# Strange_V3_2021-09-19_20-10-57.net
KiCad netlist of a schematic drawn in EasyEDA
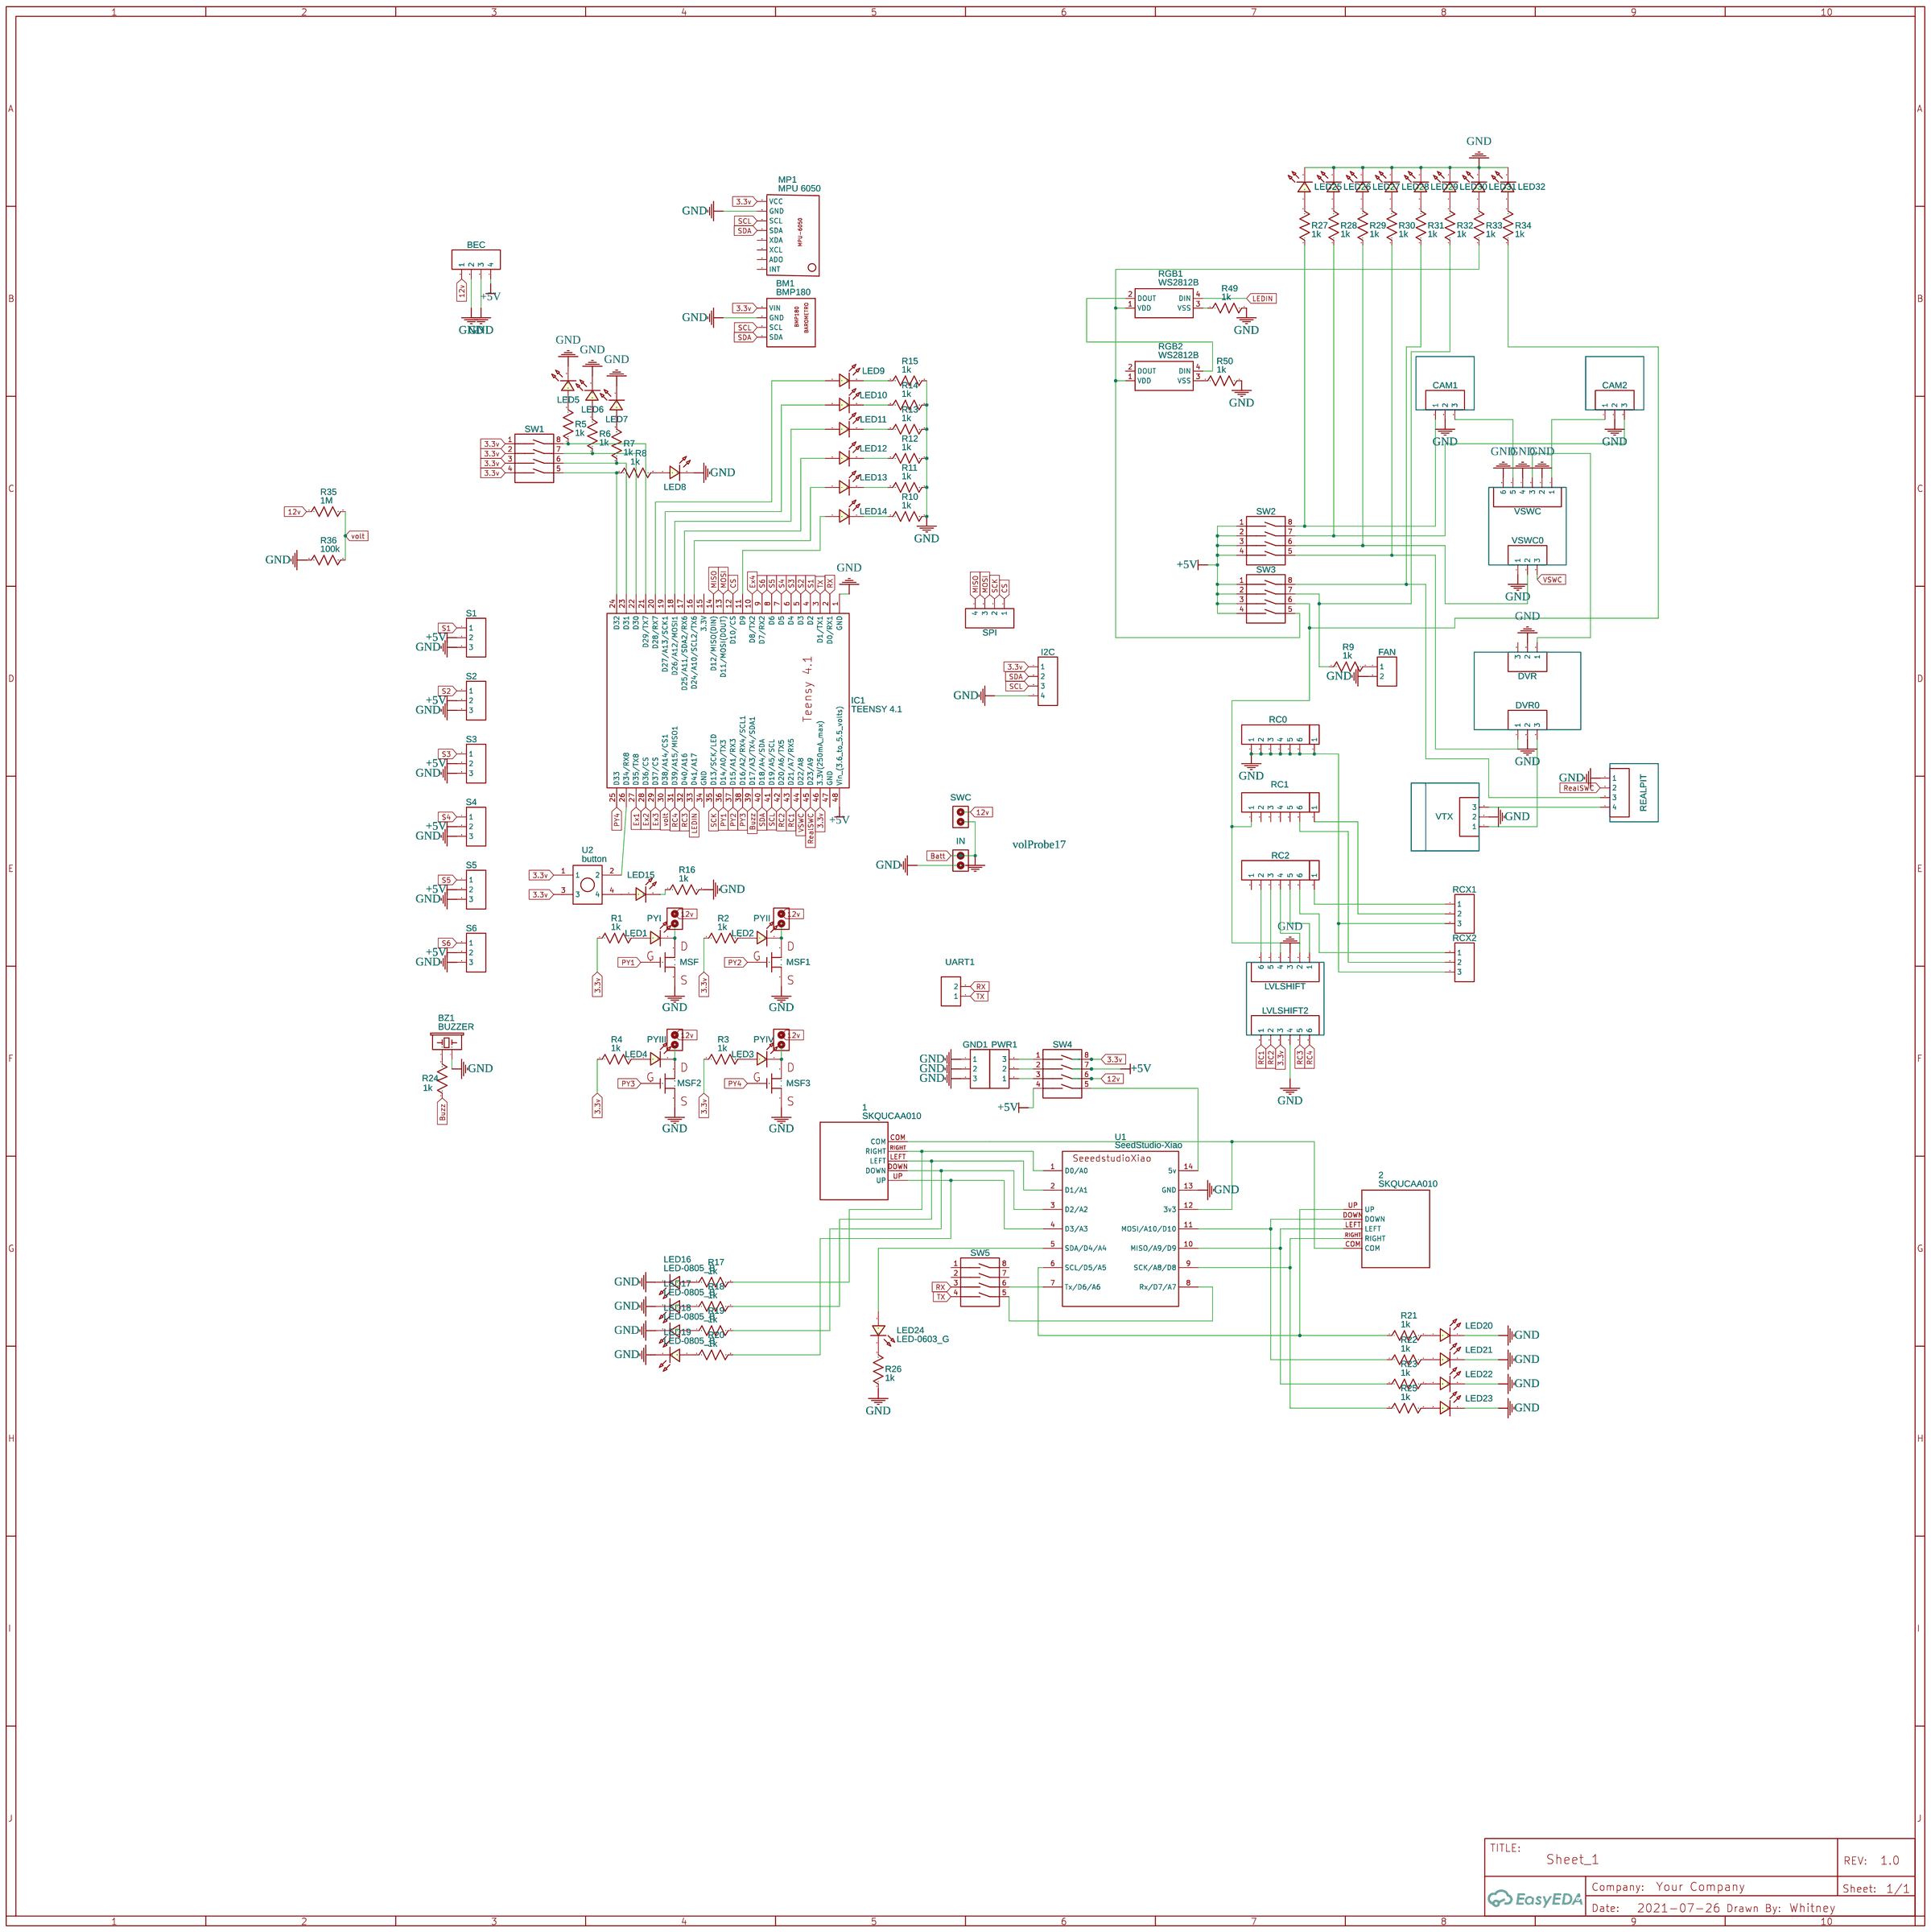
[diagram p0: schematic sheet]

(export (version "E")
  (design (tool "Eeschema 10.0.6"))
  (components
    (comp (ref "1") (value "SKQUCAA010") (libsource (lib "") (part "SKQUCAA010_1")))
    (comp (ref "2") (value "SKQUCAA010") (libsource (lib "") (part "SKQUCAA010")))
    (comp (ref "BEC")
      (value "HDR-M-2.54_1x4")
      (fields (field (name "BOM_Supplier Part") "C124378"))
      (libsource (lib "") (part "HDR-M-2.54_1x4"))
    )
    (comp (ref "BM1") (value "BMP180") (libsource (lib "") (part "BMP180")))
    (comp (ref "BZ1") (value "BUZZER") (libsource (lib "") (part "BUZZER")))
    (comp (ref "CAM1")
      (value "HDR-M-2.54_1x3")
      (fields (field (name "BOM_Supplier Part") "C180248"))
      (libsource (lib "") (part "HDR-M-2.54_1x3_6"))
    )
    (comp (ref "CAM2")
      (value "HDR-M-2.54_1x3")
      (fields (field (name "BOM_Supplier Part") "C180248"))
      (libsource (lib "") (part "HDR-M-2.54_1x3_6"))
    )
    (comp (ref "DVR")
      (value "HDR-M-2.54_1x3")
      (fields (field (name "BOM_Supplier Part") "C180248"))
      (libsource (lib "") (part "HDR-M-2.54_1x3_8"))
    )
    (comp (ref "DVR0")
      (value "HDR-M-2.54_1x3")
      (fields (field (name "BOM_Supplier Part") "C180248"))
      (libsource (lib "") (part "HDR-M-2.54_1x3_3"))
    )
    (comp (ref "FAN")
      (value "HDR-M-2.54_1x2")
      (fields (field (name "BOM_Supplier Part") "C124375"))
      (libsource (lib "") (part "HDR-M-2.54_1x2"))
    )
    (comp (ref "GND1")
      (value "HDR-M-2.54_1x3")
      (fields (field (name "BOM_Supplier Part") "C180248"))
      (libsource (lib "") (part "HDR-M-2.54_1x3"))
    )
    (comp (ref "I2C")
      (value "HDR-M-2.54_1x4")
      (fields (field (name "BOM_Supplier Part") "C124378"))
      (libsource (lib "") (part "HDR-M-2.54_1x4_3"))
    )
    (comp (ref "IC1")
      (value "TEENSY 4.1")
      (fields
        (field (name "BOM_Manufacturer Part") "Teensy 4.1")
        (field (name "BOM_Supplier Part") "474-DEV-16771")
      )
      (libsource (lib "") (part "TEENSY 4.1"))
    )
    (comp (ref "IN") (value "Screw terminal 2x1") (libsource (lib "") (part "Screw terminal 2x1_3")))
    (comp (ref "J6")
      (value "HDR-M-2.54_1x1")
      (fields (field (name "BOM_Supplier Part") "C81276"))
      (libsource (lib "") (part "HDR-M-2.54_1x1"))
    )
    (comp (ref "J10")
      (value "HDR-M-2.54_1x1")
      (fields (field (name "BOM_Supplier Part") "C81276"))
      (libsource (lib "") (part "HDR-M-2.54_1x1"))
    )
    (comp (ref "J11")
      (value "HDR-M-2.54_1x1")
      (fields (field (name "BOM_Supplier Part") "C81276"))
      (libsource (lib "") (part "HDR-M-2.54_1x1"))
    )
    (comp (ref "LED1")
      (value "LED-0805_G")
      (fields (field (name "BOM_Manufacturer Part") "NCD0805G1") (field (name "BOM_Supplier Part") "C84260"))
      (libsource (lib "") (part "LED-0805_G_1"))
    )
    (comp (ref "LED2")
      (value "LED-0805_G")
      (fields (field (name "BOM_Manufacturer Part") "NCD0805G1") (field (name "BOM_Supplier Part") "C84260"))
      (libsource (lib "") (part "LED-0805_G_1"))
    )
    (comp (ref "LED3")
      (value "LED-0805_G")
      (fields (field (name "BOM_Manufacturer Part") "NCD0805G1") (field (name "BOM_Supplier Part") "C84260"))
      (libsource (lib "") (part "LED-0805_G_1"))
    )
    (comp (ref "LED4")
      (value "LED-0805_G")
      (fields (field (name "BOM_Manufacturer Part") "NCD0805G1") (field (name "BOM_Supplier Part") "C84260"))
      (libsource (lib "") (part "LED-0805_G_1"))
    )
    (comp (ref "LED5")
      (value "LED-0805_G")
      (fields (field (name "BOM_Manufacturer Part") "NCD0805G1") (field (name "BOM_Supplier Part") "C84260"))
      (libsource (lib "") (part "LED-0805_G"))
    )
    (comp (ref "LED6")
      (value "LED-0805_G")
      (fields (field (name "BOM_Manufacturer Part") "NCD0805G1") (field (name "BOM_Supplier Part") "C84260"))
      (libsource (lib "") (part "LED-0805_G"))
    )
    (comp (ref "LED7")
      (value "LED-0805_G")
      (fields (field (name "BOM_Manufacturer Part") "NCD0805G1") (field (name "BOM_Supplier Part") "C84260"))
      (libsource (lib "") (part "LED-0805_G"))
    )
    (comp (ref "LED8")
      (value "LED-0805_G")
      (fields (field (name "BOM_Manufacturer Part") "NCD0805G1") (field (name "BOM_Supplier Part") "C84260"))
      (libsource (lib "") (part "LED-0805_G_1"))
    )
    (comp (ref "LED9")
      (value "LED-0603_R")
      (fields
        (field (name "BOM_Manufacturer Part") "19-217/R6C-AL1M2VY/3T")
        (field (name "BOM_Supplier Part") "C72044")
      )
      (libsource (lib "") (part "LED-0603_R"))
    )
    (comp (ref "LED10")
      (value "LED-0603_R")
      (fields
        (field (name "BOM_Manufacturer Part") "19-217/R6C-AL1M2VY/3T")
        (field (name "BOM_Supplier Part") "C72044")
      )
      (libsource (lib "") (part "LED-0603_R"))
    )
    (comp (ref "LED11")
      (value "LED-0603_R")
      (fields
        (field (name "BOM_Manufacturer Part") "19-217/R6C-AL1M2VY/3T")
        (field (name "BOM_Supplier Part") "C72044")
      )
      (libsource (lib "") (part "LED-0603_R"))
    )
    (comp (ref "LED12")
      (value "LED-0603_R")
      (fields
        (field (name "BOM_Manufacturer Part") "19-217/R6C-AL1M2VY/3T")
        (field (name "BOM_Supplier Part") "C72044")
      )
      (libsource (lib "") (part "LED-0603_R"))
    )
    (comp (ref "LED13")
      (value "LED-0603_R")
      (fields
        (field (name "BOM_Manufacturer Part") "19-217/R6C-AL1M2VY/3T")
        (field (name "BOM_Supplier Part") "C72044")
      )
      (libsource (lib "") (part "LED-0603_R"))
    )
    (comp (ref "LED14")
      (value "LED-0603_R")
      (fields
        (field (name "BOM_Manufacturer Part") "19-217/R6C-AL1M2VY/3T")
        (field (name "BOM_Supplier Part") "C72044")
      )
      (libsource (lib "") (part "LED-0603_R"))
    )
    (comp (ref "LED15")
      (value "LED-0603_R")
      (fields
        (field (name "BOM_Manufacturer Part") "19-217/R6C-AL1M2VY/3T")
        (field (name "BOM_Supplier Part") "C72044")
      )
      (libsource (lib "") (part "LED-0603_R"))
    )
    (comp (ref "LED16")
      (value "LED-0805_B")
      (fields
        (field (name "BOM_Manufacturer Part") "D-B080508B1-KS2")
        (field (name "BOM_Supplier Part") "C108412")
      )
      (libsource (lib "") (part "LED-0805_B"))
    )
    (comp (ref "LED17")
      (value "LED-0805_B")
      (fields
        (field (name "BOM_Manufacturer Part") "D-B080508B1-KS2")
        (field (name "BOM_Supplier Part") "C108412")
      )
      (libsource (lib "") (part "LED-0805_B"))
    )
    (comp (ref "LED18")
      (value "LED-0805_B")
      (fields
        (field (name "BOM_Manufacturer Part") "D-B080508B1-KS2")
        (field (name "BOM_Supplier Part") "C108412")
      )
      (libsource (lib "") (part "LED-0805_B"))
    )
    (comp (ref "LED19")
      (value "LED-0805_B")
      (fields
        (field (name "BOM_Manufacturer Part") "D-B080508B1-KS2")
        (field (name "BOM_Supplier Part") "C108412")
      )
      (libsource (lib "") (part "LED-0805_B"))
    )
    (comp (ref "LED20")
      (value "LED-0805_B")
      (fields
        (field (name "BOM_Manufacturer Part") "D-B080508B1-KS2")
        (field (name "BOM_Supplier Part") "C108412")
      )
      (libsource (lib "") (part "LED-0805_B_1"))
    )
    (comp (ref "LED21")
      (value "LED-0805_B")
      (fields
        (field (name "BOM_Manufacturer Part") "D-B080508B1-KS2")
        (field (name "BOM_Supplier Part") "C108412")
      )
      (libsource (lib "") (part "LED-0805_B_1"))
    )
    (comp (ref "LED22")
      (value "LED-0805_B")
      (fields
        (field (name "BOM_Manufacturer Part") "D-B080508B1-KS2")
        (field (name "BOM_Supplier Part") "C108412")
      )
      (libsource (lib "") (part "LED-0805_B_1"))
    )
    (comp (ref "LED23")
      (value "LED-0805_B")
      (fields
        (field (name "BOM_Manufacturer Part") "D-B080508B1-KS2")
        (field (name "BOM_Supplier Part") "C108412")
      )
      (libsource (lib "") (part "LED-0805_B_1"))
    )
    (comp (ref "LED24")
      (value "LED-0603_G")
      (fields
        (field (name "BOM_Manufacturer Part") "19-217/GHC-YR1S2/3T")
        (field (name "BOM_Supplier Part") "C72043")
      )
      (libsource (lib "") (part "LED-0603_G"))
    )
    (comp (ref "LED25")
      (value "LED-TH-3mm_R")
      (fields
        (field (name "BOM_Manufacturer Part") "204-10SDRD/S530-A3-L")
        (field (name "BOM_Supplier Part") "C84774")
      )
      (libsource (lib "") (part "LED-TH-3mm_R"))
    )
    (comp (ref "LED26")
      (value "LED-TH-3mm_R")
      (fields
        (field (name "BOM_Manufacturer Part") "204-10SDRD/S530-A3-L")
        (field (name "BOM_Supplier Part") "C84774")
      )
      (libsource (lib "") (part "LED-TH-3mm_R"))
    )
    (comp (ref "LED27")
      (value "LED-TH-3mm_R")
      (fields
        (field (name "BOM_Manufacturer Part") "204-10SDRD/S530-A3-L")
        (field (name "BOM_Supplier Part") "C84774")
      )
      (libsource (lib "") (part "LED-TH-3mm_R"))
    )
    (comp (ref "LED28")
      (value "LED-TH-3mm_R")
      (fields
        (field (name "BOM_Manufacturer Part") "204-10SDRD/S530-A3-L")
        (field (name "BOM_Supplier Part") "C84774")
      )
      (libsource (lib "") (part "LED-TH-3mm_R"))
    )
    (comp (ref "LED29")
      (value "LED-TH-3mm_R")
      (fields
        (field (name "BOM_Manufacturer Part") "204-10SDRD/S530-A3-L")
        (field (name "BOM_Supplier Part") "C84774")
      )
      (libsource (lib "") (part "LED-TH-3mm_R"))
    )
    (comp (ref "LED30")
      (value "LED-TH-3mm_R")
      (fields
        (field (name "BOM_Manufacturer Part") "204-10SDRD/S530-A3-L")
        (field (name "BOM_Supplier Part") "C84774")
      )
      (libsource (lib "") (part "LED-TH-3mm_R"))
    )
    (comp (ref "LED31")
      (value "LED-TH-3mm_R")
      (fields
        (field (name "BOM_Manufacturer Part") "204-10SDRD/S530-A3-L")
        (field (name "BOM_Supplier Part") "C84774")
      )
      (libsource (lib "") (part "LED-TH-3mm_R"))
    )
    (comp (ref "LED32")
      (value "LED-TH-3mm_R")
      (fields
        (field (name "BOM_Manufacturer Part") "204-10SDRD/S530-A3-L")
        (field (name "BOM_Supplier Part") "C84774")
      )
      (libsource (lib "") (part "LED-TH-3mm_R"))
    )
    (comp (ref "LVLSHIFT")
      (value "HDR-M-2.54_1x6")
      (fields (field (name "BOM_Supplier Part") "C190819"))
      (libsource (lib "") (part "HDR-M-2.54_1x6_3"))
    )
    (comp (ref "LVLSHIFT2")
      (value "HDR-M-2.54_1x6")
      (fields (field (name "BOM_Supplier Part") "C190819"))
      (libsource (lib "") (part "HDR-M-2.54_1x6_1"))
    )
    (comp (ref "MP1") (value "MPU 6050") (libsource (lib "") (part "MPU 6050")))
    (comp (ref "MSF") (value "RFP30N06LE") (libsource (lib "") (part "RFP30N06LE")))
    (comp (ref "MSF1") (value "RFP30N06LE") (libsource (lib "") (part "RFP30N06LE")))
    (comp (ref "MSF2") (value "RFP30N06LE") (libsource (lib "") (part "RFP30N06LE")))
    (comp (ref "MSF3") (value "RFP30N06LE") (libsource (lib "") (part "RFP30N06LE")))
    (comp (ref "PWR1")
      (value "HDR-M-2.54_1x3")
      (fields (field (name "BOM_Supplier Part") "C180248"))
      (libsource (lib "") (part "HDR-M-2.54_1x3_7"))
    )
    (comp (ref "PYI") (value "Screw terminal 2x1") (libsource (lib "") (part "Screw terminal 2x1")))
    (comp (ref "PYII") (value "Screw terminal 2x1") (libsource (lib "") (part "Screw terminal 2x1_2")))
    (comp (ref "PYIII") (value "Screw terminal 2x1") (libsource (lib "") (part "Screw terminal 2x1_4")))
    (comp (ref "PYIV") (value "Screw terminal 2x1") (libsource (lib "") (part "Screw terminal 2x1_1")))
    (comp (ref "R1") (value "1k") (libsource (lib "") (part "R_AXIAL-0.3_US_1")))
    (comp (ref "R2") (value "1k") (libsource (lib "") (part "R_AXIAL-0.3_US_1")))
    (comp (ref "R3") (value "1k") (libsource (lib "") (part "R_AXIAL-0.3_US_1")))
    (comp (ref "R4") (value "1k") (libsource (lib "") (part "R_AXIAL-0.3_US_1")))
    (comp (ref "R5") (value "1k") (libsource (lib "") (part "R_AXIAL-0.3_US")))
    (comp (ref "R6") (value "1k") (libsource (lib "") (part "R_AXIAL-0.3_US")))
    (comp (ref "R7") (value "1k") (libsource (lib "") (part "R_AXIAL-0.3_US")))
    (comp (ref "R8") (value "1k") (libsource (lib "") (part "R_AXIAL-0.3_US_1")))
    (comp (ref "R9") (value "1k") (libsource (lib "") (part "R_AXIAL-0.3_US_1")))
    (comp (ref "R10") (value "1k") (libsource (lib "") (part "R_AXIAL-0.3_US_1")))
    (comp (ref "R11") (value "1k") (libsource (lib "") (part "R_AXIAL-0.3_US_1")))
    (comp (ref "R12") (value "1k") (libsource (lib "") (part "R_AXIAL-0.3_US_1")))
    (comp (ref "R13") (value "1k") (libsource (lib "") (part "R_AXIAL-0.3_US_1")))
    (comp (ref "R14") (value "1k") (libsource (lib "") (part "R_AXIAL-0.3_US_1")))
    (comp (ref "R15") (value "1k") (libsource (lib "") (part "R_AXIAL-0.3_US_1")))
    (comp (ref "R16") (value "1k") (libsource (lib "") (part "R_AXIAL-0.3_US_1")))
    (comp (ref "R17") (value "1k") (libsource (lib "") (part "R_0603_US")))
    (comp (ref "R18") (value "1k") (libsource (lib "") (part "R_0603_US")))
    (comp (ref "R19") (value "1k") (libsource (lib "") (part "R_0603_US")))
    (comp (ref "R20") (value "1k") (libsource (lib "") (part "R_0603_US")))
    (comp (ref "R21") (value "1k") (libsource (lib "") (part "R_0603_US")))
    (comp (ref "R22") (value "1k") (libsource (lib "") (part "R_0603_US")))
    (comp (ref "R23") (value "1k") (libsource (lib "") (part "R_0603_US")))
    (comp (ref "R24") (value "1k") (libsource (lib "") (part "R_AXIAL-0.3_US")))
    (comp (ref "R25") (value "1k") (libsource (lib "") (part "R_0603_US")))
    (comp (ref "R26") (value "1k") (libsource (lib "") (part "R_0603_US_1")))
    (comp (ref "R27") (value "1k") (libsource (lib "") (part "R_AXIAL-0.3_US")))
    (comp (ref "R28") (value "1k") (libsource (lib "") (part "R_AXIAL-0.3_US")))
    (comp (ref "R29") (value "1k") (libsource (lib "") (part "R_AXIAL-0.3_US")))
    (comp (ref "R30") (value "1k") (libsource (lib "") (part "R_AXIAL-0.3_US")))
    (comp (ref "R31") (value "1k") (libsource (lib "") (part "R_AXIAL-0.3_US")))
    (comp (ref "R32") (value "1k") (libsource (lib "") (part "R_AXIAL-0.3_US")))
    (comp (ref "R33") (value "1k") (libsource (lib "") (part "R_AXIAL-0.3_US")))
    (comp (ref "R34") (value "1k") (libsource (lib "") (part "R_AXIAL-0.3_US")))
    (comp (ref "R35") (value "1M") (libsource (lib "") (part "R_AXIAL-0.3_US_1")))
    (comp (ref "R36") (value "100k") (libsource (lib "") (part "R_AXIAL-0.3_US_1")))
    (comp (ref "R49") (value "1k") (libsource (lib "") (part "R_0603_US")))
    (comp (ref "R50") (value "1k") (libsource (lib "") (part "R_0603_US")))
    (comp (ref "RC0")
      (value "HDR-M-2.54_1x6")
      (fields (field (name "BOM_Supplier Part") "C190819"))
      (libsource (lib "") (part "HDR-M-2.54_1x6_2"))
    )
    (comp (ref "RC1")
      (value "HDR-M-2.54_1x6")
      (fields (field (name "BOM_Supplier Part") "C190819"))
      (libsource (lib "") (part "HDR-M-2.54_1x6_2"))
    )
    (comp (ref "RC2")
      (value "HDR-M-2.54_1x6")
      (fields (field (name "BOM_Supplier Part") "C190819"))
      (libsource (lib "") (part "HDR-M-2.54_1x6_2"))
    )
    (comp (ref "RCX1")
      (value "HDR-M-2.54_1x3")
      (fields (field (name "BOM_Supplier Part") "C180248"))
      (libsource (lib "") (part "HDR-M-2.54_1x3_1"))
    )
    (comp (ref "RCX2")
      (value "HDR-M-2.54_1x3")
      (fields (field (name "BOM_Supplier Part") "C180248"))
      (libsource (lib "") (part "HDR-M-2.54_1x3_1"))
    )
    (comp (ref "REALPIT")
      (value "HDR-M-2.54_1x4")
      (fields (field (name "BOM_Supplier Part") "C124378"))
      (libsource (lib "") (part "HDR-M-2.54_1x4_1"))
    )
    (comp (ref "RGB1") (value "WS2812B") (libsource (lib "") (part "WS2812B")))
    (comp (ref "RGB2") (value "WS2812B") (libsource (lib "") (part "WS2812B")))
    (comp (ref "S1")
      (value "HDR-M-2.54_1x3")
      (fields (field (name "BOM_Supplier Part") "C180248"))
      (libsource (lib "") (part "HDR-M-2.54_1x3_5"))
    )
    (comp (ref "S2")
      (value "HDR-M-2.54_1x3")
      (fields (field (name "BOM_Supplier Part") "C180248"))
      (libsource (lib "") (part "HDR-M-2.54_1x3_5"))
    )
    (comp (ref "S3")
      (value "HDR-M-2.54_1x3")
      (fields (field (name "BOM_Supplier Part") "C180248"))
      (libsource (lib "") (part "HDR-M-2.54_1x3_5"))
    )
    (comp (ref "S4")
      (value "HDR-M-2.54_1x3")
      (fields (field (name "BOM_Supplier Part") "C180248"))
      (libsource (lib "") (part "HDR-M-2.54_1x3_5"))
    )
    (comp (ref "S5")
      (value "HDR-M-2.54_1x3")
      (fields (field (name "BOM_Supplier Part") "C180248"))
      (libsource (lib "") (part "HDR-M-2.54_1x3_5"))
    )
    (comp (ref "S6")
      (value "HDR-M-2.54_1x3")
      (fields (field (name "BOM_Supplier Part") "C180248"))
      (libsource (lib "") (part "HDR-M-2.54_1x3_5"))
    )
    (comp (ref "SPI")
      (value "HDR-M-2.54_1x4")
      (fields (field (name "BOM_Supplier Part") "C124378"))
      (libsource (lib "") (part "HDR-M-2.54_1x4_2"))
    )
    (comp (ref "SW1")
      (value "208-4_4_POSITION_DIP_SWITCH")
      (fields (field (name "BOM_Manufacturer Part") "208-4") (field (name "BOM_Supplier Part") "CT2084-ND"))
      (libsource (lib "") (part "208-4_4_POSITION_DIP_SWITCH"))
    )
    (comp (ref "SW2")
      (value "208-4_4_POSITION_DIP_SWITCH")
      (fields (field (name "BOM_Manufacturer Part") "208-4") (field (name "BOM_Supplier Part") "CT2084-ND"))
      (libsource (lib "") (part "208-4_4_POSITION_DIP_SWITCH"))
    )
    (comp (ref "SW3")
      (value "208-4_4_POSITION_DIP_SWITCH")
      (fields (field (name "BOM_Manufacturer Part") "208-4") (field (name "BOM_Supplier Part") "CT2084-ND"))
      (libsource (lib "") (part "208-4_4_POSITION_DIP_SWITCH"))
    )
    (comp (ref "SW4")
      (value "208-4_4_POSITION_DIP_SWITCH")
      (fields (field (name "BOM_Manufacturer Part") "208-4") (field (name "BOM_Supplier Part") "CT2084-ND"))
      (libsource (lib "") (part "208-4_4_POSITION_DIP_SWITCH"))
    )
    (comp (ref "SW5")
      (value "208-4_4_POSITION_DIP_SWITCH")
      (fields (field (name "BOM_Manufacturer Part") "208-4") (field (name "BOM_Supplier Part") "CT2084-ND"))
      (libsource (lib "") (part "208-4_4_POSITION_DIP_SWITCH"))
    )
    (comp (ref "SWC") (value "Screw terminal 2x1") (libsource (lib "") (part "Screw terminal 2x1_5")))
    (comp (ref "U1")
      (value "SeedStudio-Xiao")
      (fields (field (name "BOM_Manufacturer Part") "Xiao"))
      (libsource (lib "") (part "SeedStudio-Xiao"))
    )
    (comp (ref "U2")
      (value "button")
      (fields (field (name "BOM_Manufacturer Part") "DTS-6(2)") (field (name "BOM_Supplier Part") "78-1150"))
      (libsource (lib "") (part "button"))
    )
    (comp (ref "UART1")
      (value "HDR-F-2.54_1x2")
      (fields (field (name "BOM_Supplier Part") "C49661"))
      (libsource (lib "") (part "HDR-F-2.54_1x2"))
    )
    (comp (ref "VSWC")
      (value "HDR-M-2.54_1x6")
      (fields (field (name "BOM_Supplier Part") "C190819"))
      (libsource (lib "") (part "HDR-M-2.54_1x6"))
    )
    (comp (ref "VSWC0")
      (value "HDR-M-2.54_1x3")
      (fields (field (name "BOM_Supplier Part") "C180248"))
      (libsource (lib "") (part "HDR-M-2.54_1x3_4"))
    )
    (comp (ref "VTX")
      (value "HDR-M-2.54_1x3")
      (fields (field (name "BOM_Supplier Part") "C180248"))
      (libsource (lib "") (part "HDR-M-2.54_1x3_2"))
    )
  )
  (nets
    (net (code "1") (name "+5V") (class "Default")
      (node (ref "BEC") (pin "4") (pinfunction "4_4") (pintype "unspecified"))
      (node (ref "IC1") (pin "48") (pinfunction "Vin_(3.6_to_5.5_volts)_48") (pintype "unspecified"))
      (node (ref "S1") (pin "2") (pinfunction "2_2") (pintype "input"))
      (node (ref "S2") (pin "2") (pinfunction "2_2") (pintype "input"))
      (node (ref "S3") (pin "2") (pinfunction "2_2") (pintype "input"))
      (node (ref "S4") (pin "2") (pinfunction "2_2") (pintype "input"))
      (node (ref "S5") (pin "2") (pinfunction "2_2") (pintype "input"))
      (node (ref "S6") (pin "2") (pinfunction "2_2") (pintype "input"))
      (node (ref "SW2") (pin "1") (pinfunction "1_1") (pintype "unspecified"))
      (node (ref "SW2") (pin "2") (pinfunction "2_2") (pintype "unspecified"))
      (node (ref "SW2") (pin "3") (pinfunction "3_3") (pintype "unspecified"))
      (node (ref "SW2") (pin "4") (pinfunction "4_4") (pintype "unspecified"))
      (node (ref "SW3") (pin "1") (pinfunction "1_1") (pintype "unspecified"))
      (node (ref "SW3") (pin "2") (pinfunction "2_2") (pintype "unspecified"))
      (node (ref "SW3") (pin "3") (pinfunction "3_3") (pintype "unspecified"))
      (node (ref "SW3") (pin "4") (pinfunction "4_4") (pintype "unspecified"))
      (node (ref "SW4") (pin "4") (pinfunction "4_4") (pintype "unspecified"))
      (node (ref "SW4") (pin "7") (pinfunction "7_7") (pintype "unspecified"))
    )
    (net (code "2") (name "3.3v") (class "Default")
      (node (ref "BM1") (pin "VIN") (pinfunction "VIN_VIN") (pintype "unspecified"))
      (node (ref "I2C") (pin "1") (pinfunction "1_1") (pintype "unspecified"))
      (node (ref "IC1") (pin "46") (pinfunction "3.3V(250mA_max)_46") (pintype "unspecified"))
      (node (ref "LVLSHIFT2") (pin "3") (pinfunction "3_3") (pintype "input"))
      (node (ref "MP1") (pin "VCC") (pinfunction "VCC_VCC") (pintype "unspecified"))
      (node (ref "R1") (pin "1") (pinfunction "1_1") (pintype "unspecified"))
      (node (ref "R2") (pin "1") (pinfunction "1_1") (pintype "unspecified"))
      (node (ref "R3") (pin "1") (pinfunction "1_1") (pintype "unspecified"))
      (node (ref "R4") (pin "1") (pinfunction "1_1") (pintype "unspecified"))
      (node (ref "SW1") (pin "1") (pinfunction "1_1") (pintype "unspecified"))
      (node (ref "SW1") (pin "2") (pinfunction "2_2") (pintype "unspecified"))
      (node (ref "SW1") (pin "3") (pinfunction "3_3") (pintype "unspecified"))
      (node (ref "SW1") (pin "4") (pinfunction "4_4") (pintype "unspecified"))
      (node (ref "SW4") (pin "8") (pinfunction "8_8") (pintype "unspecified"))
      (node (ref "U2") (pin "1") (pinfunction "1_1") (pintype "unspecified"))
      (node (ref "U2") (pin "3") (pinfunction "3_3") (pintype "unspecified"))
    )
    (net (code "3") (name "12v") (class "Default")
      (node (ref "BEC") (pin "1") (pinfunction "1_1") (pintype "unspecified"))
      (node (ref "PYI") (pin "1") (pinfunction "1_1") (pintype "unspecified"))
      (node (ref "PYII") (pin "1") (pinfunction "1_1") (pintype "unspecified"))
      (node (ref "PYIII") (pin "1") (pinfunction "1_1") (pintype "unspecified"))
      (node (ref "PYIV") (pin "1") (pinfunction "1_1") (pintype "unspecified"))
      (node (ref "R35") (pin "1") (pinfunction "1_1") (pintype "unspecified"))
      (node (ref "SW4") (pin "6") (pinfunction "6_6") (pintype "unspecified"))
      (node (ref "SWC") (pin "1") (pinfunction "1_1") (pintype "unspecified"))
    )
    (net (code "4") (name "Batt") (class "Default")
      (node (ref "IN") (pin "1") (pinfunction "1_1") (pintype "unspecified"))
      (node (ref "SWC") (pin "2") (pinfunction "2_2") (pintype "unspecified"))
    )
    (net (code "5") (name "Buzz") (class "Default")
      (node (ref "IC1") (pin "39") (pinfunction "D17/A3/TX4/SDA1_39") (pintype "unspecified"))
      (node (ref "R24") (pin "1") (pinfunction "1_1") (pintype "unspecified"))
    )
    (net (code "6") (name "CS") (class "Default")
      (node (ref "IC1") (pin "12") (pinfunction "D10/CS_12") (pintype "unspecified"))
      (node (ref "SPI") (pin "1") (pinfunction "1_1") (pintype "unspecified"))
    )
    (net (code "7") (name "Ex1") (class "Default")
      (node (ref "IC1") (pin "27") (pinfunction "D35/TX8_27") (pintype "unspecified"))
    )
    (net (code "8") (name "Ex2") (class "Default")
      (node (ref "IC1") (pin "28") (pinfunction "D36/CS_28") (pintype "unspecified"))
    )
    (net (code "9") (name "Ex3") (class "Default")
      (node (ref "IC1") (pin "29") (pinfunction "D37/CS_29") (pintype "unspecified"))
    )
    (net (code "10") (name "Ex4") (class "Default")
      (node (ref "IC1") (pin "10") (pinfunction "D8/TX2_10") (pintype "unspecified"))
    )
    (net (code "11") (name "GND") (class "Default")
      (node (ref "BEC") (pin "2") (pinfunction "2_2") (pintype "unspecified"))
      (node (ref "BEC") (pin "3") (pinfunction "3_3") (pintype "unspecified"))
      (node (ref "BM1") (pin "GND") (pinfunction "GND_GND") (pintype "unspecified"))
      (node (ref "BZ1") (pin "-") (pinfunction "2_-") (pintype "unspecified"))
      (node (ref "CAM1") (pin "2") (pinfunction "2_2") (pintype "input"))
      (node (ref "CAM2") (pin "2") (pinfunction "2_2") (pintype "input"))
      (node (ref "DVR") (pin "2") (pinfunction "2_2") (pintype "input"))
      (node (ref "DVR0") (pin "2") (pinfunction "2_2") (pintype "input"))
      (node (ref "FAN") (pin "2") (pinfunction "2_2") (pintype "unspecified"))
      (node (ref "GND1") (pin "1") (pinfunction "1_1") (pintype "input"))
      (node (ref "GND1") (pin "2") (pinfunction "2_2") (pintype "input"))
      (node (ref "GND1") (pin "3") (pinfunction "3_3") (pintype "input"))
      (node (ref "I2C") (pin "4") (pinfunction "4_4") (pintype "unspecified"))
      (node (ref "IC1") (pin "1") (pinfunction "GND_1") (pintype "unspecified"))
      (node (ref "IN") (pin "2") (pinfunction "2_2") (pintype "unspecified"))
      (node (ref "J6") (pin "1") (pinfunction "1_1") (pintype "input"))
      (node (ref "LED16") (pin "2") (pinfunction "2_2") (pintype "unspecified"))
      (node (ref "LED17") (pin "2") (pinfunction "2_2") (pintype "unspecified"))
      (node (ref "LED18") (pin "2") (pinfunction "2_2") (pintype "unspecified"))
      (node (ref "LED19") (pin "2") (pinfunction "2_2") (pintype "unspecified"))
      (node (ref "LED20") (pin "2") (pinfunction "2_2") (pintype "unspecified"))
      (node (ref "LED21") (pin "2") (pinfunction "2_2") (pintype "unspecified"))
      (node (ref "LED22") (pin "2") (pinfunction "2_2") (pintype "unspecified"))
      (node (ref "LED23") (pin "2") (pinfunction "2_2") (pintype "unspecified"))
      (node (ref "LED25") (pin "2") (pinfunction "2_2") (pintype "unspecified"))
      (node (ref "LED26") (pin "2") (pinfunction "2_2") (pintype "unspecified"))
      (node (ref "LED27") (pin "2") (pinfunction "2_2") (pintype "unspecified"))
      (node (ref "LED28") (pin "2") (pinfunction "2_2") (pintype "unspecified"))
      (node (ref "LED29") (pin "2") (pinfunction "2_2") (pintype "unspecified"))
      (node (ref "LED30") (pin "2") (pinfunction "2_2") (pintype "unspecified"))
      (node (ref "LED31") (pin "2") (pinfunction "2_2") (pintype "unspecified"))
      (node (ref "LED32") (pin "2") (pinfunction "2_2") (pintype "unspecified"))
      (node (ref "LED5") (pin "2") (pinfunction "2_2") (pintype "unspecified"))
      (node (ref "LED6") (pin "2") (pinfunction "2_2") (pintype "unspecified"))
      (node (ref "LED7") (pin "2") (pinfunction "2_2") (pintype "unspecified"))
      (node (ref "LED8") (pin "2") (pinfunction "2_2") (pintype "unspecified"))
      (node (ref "LVLSHIFT") (pin "3") (pinfunction "3_3") (pintype "input"))
      (node (ref "LVLSHIFT2") (pin "4") (pinfunction "4_4") (pintype "input"))
      (node (ref "MP1") (pin "GND") (pinfunction "GND_GND") (pintype "unspecified"))
      (node (ref "MSF") (pin "3") (pinfunction "S_3") (pintype "unspecified"))
      (node (ref "MSF1") (pin "3") (pinfunction "S_3") (pintype "unspecified"))
      (node (ref "MSF2") (pin "3") (pinfunction "S_3") (pintype "unspecified"))
      (node (ref "MSF3") (pin "3") (pinfunction "S_3") (pintype "unspecified"))
      (node (ref "R10") (pin "2") (pinfunction "2_2") (pintype "unspecified"))
      (node (ref "R11") (pin "2") (pinfunction "2_2") (pintype "unspecified"))
      (node (ref "R12") (pin "2") (pinfunction "2_2") (pintype "unspecified"))
      (node (ref "R13") (pin "2") (pinfunction "2_2") (pintype "unspecified"))
      (node (ref "R14") (pin "2") (pinfunction "2_2") (pintype "unspecified"))
      (node (ref "R15") (pin "2") (pinfunction "2_2") (pintype "unspecified"))
      (node (ref "R16") (pin "2") (pinfunction "2_2") (pintype "unspecified"))
      (node (ref "R26") (pin "1") (pinfunction "1_1") (pintype "unspecified"))
      (node (ref "R36") (pin "1") (pinfunction "1_1") (pintype "unspecified"))
      (node (ref "R49") (pin "2") (pinfunction "2_2") (pintype "unspecified"))
      (node (ref "R50") (pin "2") (pinfunction "2_2") (pintype "unspecified"))
      (node (ref "RC0") (pin "1") (pinfunction "1_1") (pintype "input"))
      (node (ref "RC0") (pin "2") (pinfunction "2_2") (pintype "input"))
      (node (ref "RC0") (pin "3") (pinfunction "3_3") (pintype "input"))
      (node (ref "RC0") (pin "4") (pinfunction "4_4") (pintype "input"))
      (node (ref "RC0") (pin "5") (pinfunction "5_5") (pintype "input"))
      (node (ref "RC0") (pin "6") (pinfunction "6_6") (pintype "input"))
      (node (ref "RCX1") (pin "3") (pinfunction "3_3") (pintype "input"))
      (node (ref "RCX2") (pin "3") (pinfunction "3_3") (pintype "input"))
      (node (ref "REALPIT") (pin "1") (pinfunction "1_1") (pintype "unspecified"))
      (node (ref "S1") (pin "3") (pinfunction "3_3") (pintype "input"))
      (node (ref "S2") (pin "3") (pinfunction "3_3") (pintype "input"))
      (node (ref "S3") (pin "3") (pinfunction "3_3") (pintype "input"))
      (node (ref "S4") (pin "3") (pinfunction "3_3") (pintype "input"))
      (node (ref "S5") (pin "3") (pinfunction "3_3") (pintype "input"))
      (node (ref "S6") (pin "3") (pinfunction "3_3") (pintype "input"))
      (node (ref "U1") (pin "13") (pinfunction "GND_13") (pintype "unspecified"))
      (node (ref "VSWC") (pin "2") (pinfunction "2_2") (pintype "input"))
      (node (ref "VSWC") (pin "4") (pinfunction "4_4") (pintype "input"))
      (node (ref "VSWC") (pin "6") (pinfunction "6_6") (pintype "input"))
      (node (ref "VSWC0") (pin "1") (pinfunction "1_1") (pintype "input"))
      (node (ref "VTX") (pin "2") (pinfunction "2_2") (pintype "input"))
    )
    (net (code "12") (name "LEDIN") (class "Default")
      (node (ref "IC1") (pin "33") (pinfunction "D41/A17_33") (pintype "unspecified"))
      (node (ref "RGB1") (pin "4") (pinfunction "DIN_4") (pintype "input"))
    )
    (net (code "13") (name "MISO") (class "Default")
      (node (ref "IC1") (pin "14") (pinfunction "D12/MISO(DIN)_14") (pintype "unspecified"))
      (node (ref "SPI") (pin "4") (pinfunction "4_4") (pintype "unspecified"))
    )
    (net (code "14") (name "MOSI") (class "Default")
      (node (ref "IC1") (pin "13") (pinfunction "D11/MOSI(DOUT)_13") (pintype "unspecified"))
      (node (ref "SPI") (pin "3") (pinfunction "3_3") (pintype "unspecified"))
    )
    (net (code "15") (name "Net-(BZ1-1)") (class "Default")
      (node (ref "BZ1") (pin "+") (pinfunction "1_+") (pintype "unspecified"))
      (node (ref "R24") (pin "2") (pinfunction "2_2") (pintype "unspecified"))
    )
    (net (code "16") (name "Net-(CAM1-Pad1)") (class "Default")
      (node (ref "CAM1") (pin "1") (pinfunction "1_1") (pintype "input"))
      (node (ref "R27") (pin "1") (pinfunction "1_1") (pintype "unspecified"))
      (node (ref "SW2") (pin "8") (pinfunction "8_8") (pintype "unspecified"))
    )
    (net (code "17") (name "Net-(CAM1-Pad3)") (class "Default")
      (node (ref "CAM1") (pin "3") (pinfunction "3_3") (pintype "input"))
      (node (ref "VSWC") (pin "5") (pinfunction "5_5") (pintype "input"))
    )
    (net (code "18") (name "Net-(CAM2-Pad1)") (class "Default")
      (node (ref "CAM2") (pin "1") (pinfunction "1_1") (pintype "input"))
      (node (ref "VSWC") (pin "1") (pinfunction "1_1") (pintype "input"))
    )
    (net (code "19") (name "Net-(CAM2-Pad3)") (class "Default")
      (node (ref "CAM2") (pin "3") (pinfunction "3_3") (pintype "input"))
      (node (ref "R28") (pin "1") (pinfunction "1_1") (pintype "unspecified"))
      (node (ref "SW2") (pin "7") (pinfunction "7_7") (pintype "unspecified"))
    )
    (net (code "20") (name "Net-(DVR-Pad1)") (class "Default")
      (node (ref "DVR") (pin "1") (pinfunction "1_1") (pintype "input"))
      (node (ref "VSWC") (pin "3") (pinfunction "3_3") (pintype "input"))
    )
    (net (code "21") (name "Net-(DVR0-Pad1)") (class "Default")
      (node (ref "DVR0") (pin "1") (pinfunction "1_1") (pintype "input"))
      (node (ref "R30") (pin "1") (pinfunction "1_1") (pintype "unspecified"))
      (node (ref "SW2") (pin "5") (pinfunction "5_5") (pintype "unspecified"))
    )
    (net (code "22") (name "Net-(DVR0-Pad3)") (class "Default")
      (node (ref "DVR0") (pin "3") (pinfunction "3_3") (pintype "input"))
      (node (ref "VTX") (pin "1") (pinfunction "1_1") (pintype "input"))
    )
    (net (code "23") (name "Net-(FAN-Pad1)") (class "Default")
      (node (ref "FAN") (pin "1") (pinfunction "1_1") (pintype "unspecified"))
      (node (ref "R9") (pin "2") (pinfunction "2_2") (pintype "unspecified"))
    )
    (net (code "24") (name "Net-(IC1-D9)") (class "Default")
      (node (ref "IC1") (pin "11") (pinfunction "D9_11") (pintype "unspecified"))
      (node (ref "LED14") (pin "1") (pinfunction "1_1") (pintype "unspecified"))
    )
    (net (code "25") (name "Net-(IC1-D24{slash}A10{slash}SCL2{slash}TX6)") (class "Default")
      (node (ref "IC1") (pin "16") (pinfunction "D24/A10/SCL2/TX6_16") (pintype "unspecified"))
      (node (ref "LED13") (pin "1") (pinfunction "1_1") (pintype "unspecified"))
    )
    (net (code "26") (name "Net-(IC1-D25{slash}A11{slash}SDA2{slash}RX6)") (class "Default")
      (node (ref "IC1") (pin "17") (pinfunction "D25/A11/SDA2/RX6_17") (pintype "unspecified"))
      (node (ref "LED12") (pin "1") (pinfunction "1_1") (pintype "unspecified"))
    )
    (net (code "27") (name "Net-(IC1-D26{slash}A12{slash}MOSI1)") (class "Default")
      (node (ref "IC1") (pin "18") (pinfunction "D26/A12/MOSI1_18") (pintype "unspecified"))
      (node (ref "LED11") (pin "1") (pinfunction "1_1") (pintype "unspecified"))
    )
    (net (code "28") (name "Net-(IC1-D27{slash}A13{slash}SCK1)") (class "Default")
      (node (ref "IC1") (pin "19") (pinfunction "D27/A13/SCK1_19") (pintype "unspecified"))
      (node (ref "LED10") (pin "1") (pinfunction "1_1") (pintype "unspecified"))
    )
    (net (code "29") (name "Net-(IC1-D28{slash}RX7)") (class "Default")
      (node (ref "IC1") (pin "20") (pinfunction "D28/RX7_20") (pintype "unspecified"))
      (node (ref "LED9") (pin "1") (pinfunction "1_1") (pintype "unspecified"))
    )
    (net (code "30") (name "Net-(IC1-D29{slash}TX7)") (class "Default")
      (node (ref "IC1") (pin "21") (pinfunction "D29/TX7_21") (pintype "unspecified"))
      (node (ref "R5") (pin "1") (pinfunction "1_1") (pintype "unspecified"))
      (node (ref "SW1") (pin "8") (pinfunction "8_8") (pintype "unspecified"))
    )
    (net (code "31") (name "Net-(IC1-D30)") (class "Default")
      (node (ref "IC1") (pin "22") (pinfunction "D30_22") (pintype "unspecified"))
      (node (ref "R6") (pin "1") (pinfunction "1_1") (pintype "unspecified"))
      (node (ref "SW1") (pin "7") (pinfunction "7_7") (pintype "unspecified"))
    )
    (net (code "32") (name "Net-(IC1-D31)") (class "Default")
      (node (ref "IC1") (pin "23") (pinfunction "D31_23") (pintype "unspecified"))
      (node (ref "R7") (pin "1") (pinfunction "1_1") (pintype "unspecified"))
      (node (ref "SW1") (pin "6") (pinfunction "6_6") (pintype "unspecified"))
    )
    (net (code "33") (name "Net-(IC1-D32)") (class "Default")
      (node (ref "IC1") (pin "24") (pinfunction "D32_24") (pintype "unspecified"))
      (node (ref "R8") (pin "1") (pinfunction "1_1") (pintype "unspecified"))
      (node (ref "SW1") (pin "5") (pinfunction "5_5") (pintype "unspecified"))
    )
    (net (code "34") (name "Net-(IC1-D34{slash}RX8)") (class "Default")
      (node (ref "IC1") (pin "26") (pinfunction "D34/RX8_26") (pintype "unspecified"))
      (node (ref "U2") (pin "2") (pinfunction "2_2") (pintype "unspecified"))
    )
    (net (code "35") (name "Net-(J10-Pad1)") (class "Default")
      (node (ref "J10") (pin "1") (pinfunction "1_1") (pintype "input"))
      (node (ref "RCX1") (pin "2") (pinfunction "2_2") (pintype "input"))
    )
    (net (code "36") (name "Net-(J11-Pad1)") (class "Default")
      (node (ref "J11") (pin "1") (pinfunction "1_1") (pintype "input"))
      (node (ref "RCX1") (pin "1") (pinfunction "1_1") (pintype "input"))
    )
    (net (code "37") (name "Net-(LED1-Pad1)") (class "Default")
      (node (ref "LED1") (pin "1") (pinfunction "1_1") (pintype "unspecified"))
      (node (ref "R1") (pin "2") (pinfunction "2_2") (pintype "unspecified"))
    )
    (net (code "38") (name "Net-(LED2-Pad1)") (class "Default")
      (node (ref "LED2") (pin "1") (pinfunction "1_1") (pintype "unspecified"))
      (node (ref "R2") (pin "2") (pinfunction "2_2") (pintype "unspecified"))
    )
    (net (code "39") (name "Net-(LED3-Pad1)") (class "Default")
      (node (ref "LED3") (pin "1") (pinfunction "1_1") (pintype "unspecified"))
      (node (ref "R3") (pin "2") (pinfunction "2_2") (pintype "unspecified"))
    )
    (net (code "40") (name "Net-(LED4-Pad1)") (class "Default")
      (node (ref "LED4") (pin "1") (pinfunction "1_1") (pintype "unspecified"))
      (node (ref "R4") (pin "2") (pinfunction "2_2") (pintype "unspecified"))
    )
    (net (code "41") (name "Net-(LED5-Pad1)") (class "Default")
      (node (ref "LED5") (pin "1") (pinfunction "1_1") (pintype "unspecified"))
      (node (ref "R5") (pin "2") (pinfunction "2_2") (pintype "unspecified"))
    )
    (net (code "42") (name "Net-(LED6-Pad1)") (class "Default")
      (node (ref "LED6") (pin "1") (pinfunction "1_1") (pintype "unspecified"))
      (node (ref "R6") (pin "2") (pinfunction "2_2") (pintype "unspecified"))
    )
    (net (code "43") (name "Net-(LED7-Pad1)") (class "Default")
      (node (ref "LED7") (pin "1") (pinfunction "1_1") (pintype "unspecified"))
      (node (ref "R7") (pin "2") (pinfunction "2_2") (pintype "unspecified"))
    )
    (net (code "44") (name "Net-(LED8-Pad1)") (class "Default")
      (node (ref "LED8") (pin "1") (pinfunction "1_1") (pintype "unspecified"))
      (node (ref "R8") (pin "2") (pinfunction "2_2") (pintype "unspecified"))
    )
    (net (code "45") (name "Net-(LED9-Pad2)") (class "Default")
      (node (ref "LED9") (pin "2") (pinfunction "2_2") (pintype "unspecified"))
      (node (ref "R15") (pin "1") (pinfunction "1_1") (pintype "unspecified"))
    )
    (net (code "46") (name "Net-(LED10-Pad2)") (class "Default")
      (node (ref "LED10") (pin "2") (pinfunction "2_2") (pintype "unspecified"))
      (node (ref "R14") (pin "1") (pinfunction "1_1") (pintype "unspecified"))
    )
    (net (code "47") (name "Net-(LED11-Pad2)") (class "Default")
      (node (ref "LED11") (pin "2") (pinfunction "2_2") (pintype "unspecified"))
      (node (ref "R13") (pin "1") (pinfunction "1_1") (pintype "unspecified"))
    )
    (net (code "48") (name "Net-(LED12-Pad2)") (class "Default")
      (node (ref "LED12") (pin "2") (pinfunction "2_2") (pintype "unspecified"))
      (node (ref "R12") (pin "1") (pinfunction "1_1") (pintype "unspecified"))
    )
    (net (code "49") (name "Net-(LED13-Pad2)") (class "Default")
      (node (ref "LED13") (pin "2") (pinfunction "2_2") (pintype "unspecified"))
      (node (ref "R11") (pin "1") (pinfunction "1_1") (pintype "unspecified"))
    )
    (net (code "50") (name "Net-(LED14-Pad2)") (class "Default")
      (node (ref "LED14") (pin "2") (pinfunction "2_2") (pintype "unspecified"))
      (node (ref "R10") (pin "1") (pinfunction "1_1") (pintype "unspecified"))
    )
    (net (code "51") (name "Net-(LED15-Pad1)") (class "Default")
      (node (ref "LED15") (pin "1") (pinfunction "1_1") (pintype "unspecified"))
      (node (ref "U2") (pin "4") (pinfunction "4_4") (pintype "unspecified"))
    )
    (net (code "52") (name "Net-(LED15-Pad2)") (class "Default")
      (node (ref "LED15") (pin "2") (pinfunction "2_2") (pintype "unspecified"))
      (node (ref "R16") (pin "1") (pinfunction "1_1") (pintype "unspecified"))
    )
    (net (code "53") (name "Net-(LED16-Pad1)") (class "Default")
      (node (ref "LED16") (pin "1") (pinfunction "1_1") (pintype "unspecified"))
      (node (ref "R17") (pin "1") (pinfunction "1_1") (pintype "unspecified"))
    )
    (net (code "54") (name "Net-(LED17-Pad1)") (class "Default")
      (node (ref "LED17") (pin "1") (pinfunction "1_1") (pintype "unspecified"))
      (node (ref "R18") (pin "1") (pinfunction "1_1") (pintype "unspecified"))
    )
    (net (code "55") (name "Net-(LED18-Pad1)") (class "Default")
      (node (ref "LED18") (pin "1") (pinfunction "1_1") (pintype "unspecified"))
      (node (ref "R19") (pin "1") (pinfunction "1_1") (pintype "unspecified"))
    )
    (net (code "56") (name "Net-(LED19-Pad1)") (class "Default")
      (node (ref "LED19") (pin "1") (pinfunction "1_1") (pintype "unspecified"))
      (node (ref "R20") (pin "1") (pinfunction "1_1") (pintype "unspecified"))
    )
    (net (code "57") (name "Net-(LED20-Pad1)") (class "Default")
      (node (ref "LED20") (pin "1") (pinfunction "1_1") (pintype "unspecified"))
      (node (ref "R21") (pin "2") (pinfunction "2_2") (pintype "unspecified"))
    )
    (net (code "58") (name "Net-(LED21-Pad1)") (class "Default")
      (node (ref "LED21") (pin "1") (pinfunction "1_1") (pintype "unspecified"))
      (node (ref "R22") (pin "2") (pinfunction "2_2") (pintype "unspecified"))
    )
    (net (code "59") (name "Net-(LED22-Pad1)") (class "Default")
      (node (ref "LED22") (pin "1") (pinfunction "1_1") (pintype "unspecified"))
      (node (ref "R23") (pin "2") (pinfunction "2_2") (pintype "unspecified"))
    )
    (net (code "60") (name "Net-(LED23-Pad1)") (class "Default")
      (node (ref "LED23") (pin "1") (pinfunction "1_1") (pintype "unspecified"))
      (node (ref "R25") (pin "2") (pinfunction "2_2") (pintype "unspecified"))
    )
    (net (code "61") (name "Net-(LED24-Pad2)") (class "Default")
      (node (ref "LED24") (pin "2") (pinfunction "2_2") (pintype "unspecified"))
      (node (ref "R26") (pin "2") (pinfunction "2_2") (pintype "unspecified"))
    )
    (net (code "62") (name "Net-(LED25-Pad1)") (class "Default")
      (node (ref "LED25") (pin "1") (pinfunction "1_1") (pintype "unspecified"))
      (node (ref "R27") (pin "2") (pinfunction "2_2") (pintype "unspecified"))
    )
    (net (code "63") (name "Net-(LED26-Pad1)") (class "Default")
      (node (ref "LED26") (pin "1") (pinfunction "1_1") (pintype "unspecified"))
      (node (ref "R28") (pin "2") (pinfunction "2_2") (pintype "unspecified"))
    )
    (net (code "64") (name "Net-(LED27-Pad1)") (class "Default")
      (node (ref "LED27") (pin "1") (pinfunction "1_1") (pintype "unspecified"))
      (node (ref "R29") (pin "2") (pinfunction "2_2") (pintype "unspecified"))
    )
    (net (code "65") (name "Net-(LED28-Pad1)") (class "Default")
      (node (ref "LED28") (pin "1") (pinfunction "1_1") (pintype "unspecified"))
      (node (ref "R30") (pin "2") (pinfunction "2_2") (pintype "unspecified"))
    )
    (net (code "66") (name "Net-(LED29-Pad1)") (class "Default")
      (node (ref "LED29") (pin "1") (pinfunction "1_1") (pintype "unspecified"))
      (node (ref "R31") (pin "2") (pinfunction "2_2") (pintype "unspecified"))
    )
    (net (code "67") (name "Net-(LED30-Pad1)") (class "Default")
      (node (ref "LED30") (pin "1") (pinfunction "1_1") (pintype "unspecified"))
      (node (ref "R32") (pin "2") (pinfunction "2_2") (pintype "unspecified"))
    )
    (net (code "68") (name "Net-(LED31-Pad1)") (class "Default")
      (node (ref "LED31") (pin "1") (pinfunction "1_1") (pintype "unspecified"))
      (node (ref "R33") (pin "2") (pinfunction "2_2") (pintype "unspecified"))
    )
    (net (code "69") (name "Net-(LED32-Pad1)") (class "Default")
      (node (ref "LED32") (pin "1") (pinfunction "1_1") (pintype "unspecified"))
      (node (ref "R34") (pin "2") (pinfunction "2_2") (pintype "unspecified"))
    )
    (net (code "70") (name "Net-(LVLSHIFT-Pad1)") (class "Default")
      (node (ref "LVLSHIFT") (pin "1") (pinfunction "1_1") (pintype "input"))
      (node (ref "RC2") (pin "5") (pinfunction "5_5") (pintype "input"))
    )
    (net (code "71") (name "Net-(LVLSHIFT-Pad2)") (class "Default")
      (node (ref "LVLSHIFT") (pin "2") (pinfunction "2_2") (pintype "input"))
      (node (ref "RC2") (pin "4") (pinfunction "4_4") (pintype "input"))
    )
    (net (code "72") (name "Net-(LVLSHIFT-Pad4)") (class "Default")
      (node (ref "LVLSHIFT") (pin "4") (pinfunction "4_4") (pintype "input"))
      (node (ref "R34") (pin "1") (pinfunction "1_1") (pintype "unspecified"))
      (node (ref "RC1") (pin "1") (pinfunction "1_1") (pintype "input"))
      (node (ref "SW3") (pin "6") (pinfunction "6_6") (pintype "unspecified"))
    )
    (net (code "73") (name "Net-(LVLSHIFT-Pad5)") (class "Default")
      (node (ref "LVLSHIFT") (pin "5") (pinfunction "5_5") (pintype "input"))
      (node (ref "RC2") (pin "3") (pinfunction "3_3") (pintype "input"))
    )
    (net (code "74") (name "Net-(LVLSHIFT-Pad6)") (class "Default")
      (node (ref "LVLSHIFT") (pin "6") (pinfunction "6_6") (pintype "input"))
      (node (ref "RC2") (pin "2") (pinfunction "2_2") (pintype "input"))
    )
    (net (code "75") (name "Net-(MSF-D)") (class "Default")
      (node (ref "LED1") (pin "2") (pinfunction "2_2") (pintype "unspecified"))
      (node (ref "MSF") (pin "2") (pinfunction "D_2") (pintype "unspecified"))
      (node (ref "PYI") (pin "2") (pinfunction "2_2") (pintype "unspecified"))
    )
    (net (code "76") (name "Net-(MSF1-D)") (class "Default")
      (node (ref "LED2") (pin "2") (pinfunction "2_2") (pintype "unspecified"))
      (node (ref "MSF1") (pin "2") (pinfunction "D_2") (pintype "unspecified"))
      (node (ref "PYII") (pin "2") (pinfunction "2_2") (pintype "unspecified"))
    )
    (net (code "77") (name "Net-(MSF2-D)") (class "Default")
      (node (ref "LED4") (pin "2") (pinfunction "2_2") (pintype "unspecified"))
      (node (ref "MSF2") (pin "2") (pinfunction "D_2") (pintype "unspecified"))
      (node (ref "PYIII") (pin "2") (pinfunction "2_2") (pintype "unspecified"))
    )
    (net (code "78") (name "Net-(MSF3-D)") (class "Default")
      (node (ref "LED3") (pin "2") (pinfunction "2_2") (pintype "unspecified"))
      (node (ref "MSF3") (pin "2") (pinfunction "D_2") (pintype "unspecified"))
      (node (ref "PYIV") (pin "2") (pinfunction "2_2") (pintype "unspecified"))
    )
    (net (code "79") (name "Net-(PWR1-Pad1)") (class "Default")
      (node (ref "PWR1") (pin "1") (pinfunction "1_1") (pintype "input"))
      (node (ref "SW4") (pin "3") (pinfunction "3_3") (pintype "unspecified"))
    )
    (net (code "80") (name "Net-(PWR1-Pad2)") (class "Default")
      (node (ref "PWR1") (pin "2") (pinfunction "2_2") (pintype "input"))
      (node (ref "SW4") (pin "2") (pinfunction "2_2") (pintype "unspecified"))
    )
    (net (code "81") (name "Net-(PWR1-Pad3)") (class "Default")
      (node (ref "PWR1") (pin "3") (pinfunction "3_3") (pintype "input"))
      (node (ref "SW4") (pin "1") (pinfunction "1_1") (pintype "unspecified"))
    )
    (net (code "82") (name "Net-(R29-Pad1)") (class "Default")
      (node (ref "R29") (pin "1") (pinfunction "1_1") (pintype "unspecified"))
      (node (ref "SW2") (pin "6") (pinfunction "6_6") (pintype "unspecified"))
      (node (ref "VSWC0") (pin "2") (pinfunction "2_2") (pintype "input"))
    )
    (net (code "83") (name "Net-(R31-Pad1)") (class "Default")
      (node (ref "R31") (pin "1") (pinfunction "1_1") (pintype "unspecified"))
      (node (ref "REALPIT") (pin "3") (pinfunction "3_3") (pintype "unspecified"))
      (node (ref "SW3") (pin "8") (pinfunction "8_8") (pintype "unspecified"))
    )
    (net (code "84") (name "Net-(R32-Pad1)") (class "Default")
      (node (ref "R32") (pin "1") (pinfunction "1_1") (pintype "unspecified"))
      (node (ref "R9") (pin "1") (pinfunction "1_1") (pintype "unspecified"))
      (node (ref "SW3") (pin "7") (pinfunction "7_7") (pintype "unspecified"))
    )
    (net (code "85") (name "Net-(RC1-Pad6)") (class "Default")
      (node (ref "RC1") (pin "6") (pinfunction "6_6") (pintype "input"))
      (node (ref "RCX2") (pin "2") (pinfunction "2_2") (pintype "input"))
    )
    (net (code "86") (name "Net-(RC2-Pad6)") (class "Default")
      (node (ref "RC2") (pin "6") (pinfunction "6_6") (pintype "input"))
      (node (ref "RCX2") (pin "1") (pinfunction "1_1") (pintype "input"))
    )
    (net (code "87") (name "Net-(REALPIT-Pad4)") (class "Default")
      (node (ref "REALPIT") (pin "4") (pinfunction "4_4") (pintype "unspecified"))
      (node (ref "VTX") (pin "3") (pinfunction "3_3") (pintype "input"))
    )
    (net (code "88") (name "Net-(RGB1-DOUT)") (class "Default")
      (node (ref "RGB1") (pin "2") (pinfunction "DOUT_2") (pintype "output"))
      (node (ref "RGB2") (pin "4") (pinfunction "DIN_4") (pintype "input"))
    )
    (net (code "89") (name "Net-(RGB1-VDD)") (class "Default")
      (node (ref "R33") (pin "1") (pinfunction "1_1") (pintype "unspecified"))
      (node (ref "RGB1") (pin "1") (pinfunction "VDD_1") (pintype "passive"))
      (node (ref "RGB2") (pin "1") (pinfunction "VDD_1") (pintype "passive"))
      (node (ref "SW3") (pin "5") (pinfunction "5_5") (pintype "unspecified"))
    )
    (net (code "90") (name "Net-(RGB1-VSS)") (class "Default")
      (node (ref "R49") (pin "1") (pinfunction "1_1") (pintype "unspecified"))
      (node (ref "RGB1") (pin "3") (pinfunction "VSS_3") (pintype "passive"))
    )
    (net (code "91") (name "Net-(RGB2-VSS)") (class "Default")
      (node (ref "R50") (pin "1") (pinfunction "1_1") (pintype "unspecified"))
      (node (ref "RGB2") (pin "3") (pinfunction "VSS_3") (pintype "passive"))
    )
    (net (code "92") (name "Net-(U1-3v3)") (class "Default")
      (node (ref "1") (pin "COM") (pinfunction "COM_COM") (pintype "bidirectional"))
      (node (ref "2") (pin "COM") (pinfunction "COM_COM") (pintype "bidirectional"))
      (node (ref "U1") (pin "12") (pinfunction "3v3_12") (pintype "unspecified"))
    )
    (net (code "93") (name "Net-(U1-5v)") (class "Default")
      (node (ref "SW4") (pin "5") (pinfunction "5_5") (pintype "unspecified"))
      (node (ref "U1") (pin "14") (pinfunction "5v_14") (pintype "unspecified"))
    )
    (net (code "94") (name "Net-(U1-D0{slash}A0)") (class "Default")
      (node (ref "1") (pin "RIGHT") (pinfunction "RIGHT_RIGHT") (pintype "bidirectional"))
      (node (ref "R17") (pin "2") (pinfunction "2_2") (pintype "unspecified"))
      (node (ref "U1") (pin "1") (pinfunction "D0/A0_1") (pintype "unspecified"))
    )
    (net (code "95") (name "Net-(U1-D1{slash}A1)") (class "Default")
      (node (ref "1") (pin "LEFT") (pinfunction "LEFT_LEFT") (pintype "bidirectional"))
      (node (ref "R18") (pin "2") (pinfunction "2_2") (pintype "unspecified"))
      (node (ref "U1") (pin "2") (pinfunction "D1/A1_2") (pintype "unspecified"))
    )
    (net (code "96") (name "Net-(U1-D2{slash}A2)") (class "Default")
      (node (ref "1") (pin "DOWN") (pinfunction "DOWN_DOWN") (pintype "bidirectional"))
      (node (ref "R19") (pin "2") (pinfunction "2_2") (pintype "unspecified"))
      (node (ref "U1") (pin "3") (pinfunction "D2/A2_3") (pintype "unspecified"))
    )
    (net (code "97") (name "Net-(U1-D3{slash}A3)") (class "Default")
      (node (ref "1") (pin "UP") (pinfunction "UP_UP") (pintype "bidirectional"))
      (node (ref "R20") (pin "2") (pinfunction "2_2") (pintype "unspecified"))
      (node (ref "U1") (pin "4") (pinfunction "D3/A3_4") (pintype "unspecified"))
    )
    (net (code "98") (name "Net-(U1-MISO{slash}A9{slash}D9)") (class "Default")
      (node (ref "2") (pin "LEFT") (pinfunction "LEFT_LEFT") (pintype "bidirectional"))
      (node (ref "R23") (pin "1") (pinfunction "1_1") (pintype "unspecified"))
      (node (ref "U1") (pin "10") (pinfunction "MISO/A9/D9_10") (pintype "unspecified"))
    )
    (net (code "99") (name "Net-(U1-MOSI{slash}A10{slash}D10)") (class "Default")
      (node (ref "2") (pin "DOWN") (pinfunction "DOWN_DOWN") (pintype "bidirectional"))
      (node (ref "R22") (pin "1") (pinfunction "1_1") (pintype "unspecified"))
      (node (ref "U1") (pin "11") (pinfunction "MOSI/A10/D10_11") (pintype "unspecified"))
    )
    (net (code "100") (name "Net-(U1-Rx{slash}D7{slash}A7)") (class "Default")
      (node (ref "SW5") (pin "5") (pinfunction "5_5") (pintype "unspecified"))
      (node (ref "U1") (pin "8") (pinfunction "Rx/D7/A7_8") (pintype "unspecified"))
    )
    (net (code "101") (name "Net-(U1-SCK{slash}A8{slash}D8)") (class "Default")
      (node (ref "2") (pin "RIGHT") (pinfunction "RIGHT_RIGHT") (pintype "bidirectional"))
      (node (ref "R25") (pin "1") (pinfunction "1_1") (pintype "unspecified"))
      (node (ref "U1") (pin "9") (pinfunction "SCK/A8/D8_9") (pintype "unspecified"))
    )
    (net (code "102") (name "Net-(U1-SCL{slash}D5{slash}A5)") (class "Default")
      (node (ref "2") (pin "UP") (pinfunction "UP_UP") (pintype "bidirectional"))
      (node (ref "R21") (pin "1") (pinfunction "1_1") (pintype "unspecified"))
      (node (ref "U1") (pin "6") (pinfunction "SCL/D5/A5_6") (pintype "unspecified"))
    )
    (net (code "103") (name "Net-(U1-SDA{slash}D4{slash}A4)") (class "Default")
      (node (ref "LED24") (pin "1") (pinfunction "1_1") (pintype "unspecified"))
      (node (ref "U1") (pin "5") (pinfunction "SDA/D4/A4_5") (pintype "unspecified"))
    )
    (net (code "104") (name "Net-(U1-Tx{slash}D6{slash}A6)") (class "Default")
      (node (ref "SW5") (pin "6") (pinfunction "6_6") (pintype "unspecified"))
      (node (ref "U1") (pin "7") (pinfunction "Tx/D6/A6_7") (pintype "unspecified"))
    )
    (net (code "105") (name "PY1") (class "Default")
      (node (ref "IC1") (pin "36") (pinfunction "D14/A0/TX3_36") (pintype "unspecified"))
      (node (ref "MSF") (pin "1") (pinfunction "G_1") (pintype "unspecified"))
    )
    (net (code "106") (name "PY2") (class "Default")
      (node (ref "IC1") (pin "37") (pinfunction "D15/A1/RX3_37") (pintype "unspecified"))
      (node (ref "MSF1") (pin "1") (pinfunction "G_1") (pintype "unspecified"))
    )
    (net (code "107") (name "PY3") (class "Default")
      (node (ref "IC1") (pin "38") (pinfunction "D16/A2/RX4/SCL1_38") (pintype "unspecified"))
      (node (ref "MSF2") (pin "1") (pinfunction "G_1") (pintype "unspecified"))
    )
    (net (code "108") (name "PY4") (class "Default")
      (node (ref "IC1") (pin "25") (pinfunction "D33_25") (pintype "unspecified"))
      (node (ref "MSF3") (pin "1") (pinfunction "G_1") (pintype "unspecified"))
    )
    (net (code "109") (name "RC1") (class "Default")
      (node (ref "IC1") (pin "43") (pinfunction "D21/A7/RX5_43") (pintype "unspecified"))
      (node (ref "LVLSHIFT2") (pin "1") (pinfunction "1_1") (pintype "input"))
    )
    (net (code "110") (name "RC2") (class "Default")
      (node (ref "IC1") (pin "42") (pinfunction "D20/A6/TX5_42") (pintype "unspecified"))
      (node (ref "LVLSHIFT2") (pin "2") (pinfunction "2_2") (pintype "input"))
    )
    (net (code "111") (name "RC3") (class "Default")
      (node (ref "IC1") (pin "32") (pinfunction "D40/A16_32") (pintype "unspecified"))
      (node (ref "LVLSHIFT2") (pin "5") (pinfunction "5_5") (pintype "input"))
    )
    (net (code "112") (name "RC4") (class "Default")
      (node (ref "IC1") (pin "31") (pinfunction "D39/A15/MISO1_31") (pintype "unspecified"))
      (node (ref "LVLSHIFT2") (pin "6") (pinfunction "6_6") (pintype "input"))
    )
    (net (code "113") (name "RX") (class "Default")
      (node (ref "IC1") (pin "2") (pinfunction "D0/RX1_2") (pintype "unspecified"))
      (node (ref "SW5") (pin "3") (pinfunction "3_3") (pintype "unspecified"))
      (node (ref "UART1") (pin "2") (pinfunction "2_2") (pintype "input"))
    )
    (net (code "114") (name "RealSWC") (class "Default")
      (node (ref "IC1") (pin "45") (pinfunction "D23/A9_45") (pintype "unspecified"))
      (node (ref "REALPIT") (pin "2") (pinfunction "2_2") (pintype "unspecified"))
    )
    (net (code "115") (name "S1") (class "Default")
      (node (ref "IC1") (pin "4") (pinfunction "D2_4") (pintype "unspecified"))
      (node (ref "S1") (pin "1") (pinfunction "1_1") (pintype "input"))
    )
    (net (code "116") (name "S2") (class "Default")
      (node (ref "IC1") (pin "5") (pinfunction "D3_5") (pintype "unspecified"))
      (node (ref "S2") (pin "1") (pinfunction "1_1") (pintype "input"))
    )
    (net (code "117") (name "S3") (class "Default")
      (node (ref "IC1") (pin "6") (pinfunction "D4_6") (pintype "unspecified"))
      (node (ref "S3") (pin "1") (pinfunction "1_1") (pintype "input"))
    )
    (net (code "118") (name "S4") (class "Default")
      (node (ref "IC1") (pin "7") (pinfunction "D5_7") (pintype "unspecified"))
      (node (ref "S4") (pin "1") (pinfunction "1_1") (pintype "input"))
    )
    (net (code "119") (name "S5") (class "Default")
      (node (ref "IC1") (pin "8") (pinfunction "D6_8") (pintype "unspecified"))
      (node (ref "S5") (pin "1") (pinfunction "1_1") (pintype "input"))
    )
    (net (code "120") (name "S6") (class "Default")
      (node (ref "IC1") (pin "9") (pinfunction "D7/RX2_9") (pintype "unspecified"))
      (node (ref "S6") (pin "1") (pinfunction "1_1") (pintype "input"))
    )
    (net (code "121") (name "SCK") (class "Default")
      (node (ref "IC1") (pin "35") (pinfunction "D13/SCK/LED_35") (pintype "unspecified"))
      (node (ref "SPI") (pin "2") (pinfunction "2_2") (pintype "unspecified"))
    )
    (net (code "122") (name "SCL") (class "Default")
      (node (ref "BM1") (pin "SCL") (pinfunction "SCL_SCL") (pintype "unspecified"))
      (node (ref "I2C") (pin "3") (pinfunction "3_3") (pintype "unspecified"))
      (node (ref "IC1") (pin "41") (pinfunction "D19/A5/SCL_41") (pintype "unspecified"))
      (node (ref "MP1") (pin "SCL") (pinfunction "SCL_SCL") (pintype "unspecified"))
    )
    (net (code "123") (name "SDA") (class "Default")
      (node (ref "BM1") (pin "SDA") (pinfunction "SDA_SDA") (pintype "unspecified"))
      (node (ref "I2C") (pin "2") (pinfunction "2_2") (pintype "unspecified"))
      (node (ref "IC1") (pin "40") (pinfunction "D18/A4/SDA_40") (pintype "unspecified"))
      (node (ref "MP1") (pin "SDA") (pinfunction "SDA_SDA") (pintype "unspecified"))
    )
    (net (code "124") (name "TX") (class "Default")
      (node (ref "IC1") (pin "3") (pinfunction "D1/TX1_3") (pintype "unspecified"))
      (node (ref "SW5") (pin "4") (pinfunction "4_4") (pintype "unspecified"))
      (node (ref "UART1") (pin "1") (pinfunction "1_1") (pintype "input"))
    )
    (net (code "125") (name "VSWC") (class "Default")
      (node (ref "IC1") (pin "44") (pinfunction "D22/A8_44") (pintype "unspecified"))
      (node (ref "VSWC0") (pin "3") (pinfunction "3_3") (pintype "input"))
    )
    (net (code "126") (name "unconnected-(DVR-Pad3)") (class "Default")
      (node (ref "DVR") (pin "3") (pinfunction "3_3") (pintype "input"))
    )
    (net (code "127") (name "unconnected-(IC1-3.3V-Pad15)") (class "Default")
      (node (ref "IC1") (pin "15") (pinfunction "3.3V_15") (pintype "unspecified"))
    )
    (net (code "128") (name "unconnected-(IC1-GND-Pad34)") (class "Default")
      (node (ref "IC1") (pin "34") (pinfunction "GND_34") (pintype "unspecified"))
    )
    (net (code "129") (name "unconnected-(IC1-GND-Pad47)") (class "Default")
      (node (ref "IC1") (pin "47") (pinfunction "GND_47") (pintype "unspecified"))
    )
    (net (code "130") (name "unconnected-(MP1-PadADO)") (class "Default")
      (node (ref "MP1") (pin "ADO") (pinfunction "ADO_ADO") (pintype "unspecified"))
    )
    (net (code "131") (name "unconnected-(MP1-PadINT)") (class "Default")
      (node (ref "MP1") (pin "INT") (pinfunction "INT_INT") (pintype "unspecified"))
    )
    (net (code "132") (name "unconnected-(MP1-PadXCL)") (class "Default")
      (node (ref "MP1") (pin "XCL") (pinfunction "XCL_XCL") (pintype "unspecified"))
    )
    (net (code "133") (name "unconnected-(MP1-PadXDA)") (class "Default")
      (node (ref "MP1") (pin "XDA") (pinfunction "XDA_XDA") (pintype "unspecified"))
    )
    (net (code "134") (name "unconnected-(RC1-Pad2)") (class "Default")
      (node (ref "RC1") (pin "2") (pinfunction "2_2") (pintype "input"))
    )
    (net (code "135") (name "unconnected-(RC1-Pad3)") (class "Default")
      (node (ref "RC1") (pin "3") (pinfunction "3_3") (pintype "input"))
    )
    (net (code "136") (name "unconnected-(RC1-Pad4)") (class "Default")
      (node (ref "RC1") (pin "4") (pinfunction "4_4") (pintype "input"))
    )
    (net (code "137") (name "unconnected-(RC1-Pad5)") (class "Default")
      (node (ref "RC1") (pin "5") (pinfunction "5_5") (pintype "input"))
    )
    (net (code "138") (name "unconnected-(RC2-Pad1)") (class "Default")
      (node (ref "RC2") (pin "1") (pinfunction "1_1") (pintype "input"))
    )
    (net (code "139") (name "unconnected-(RGB2-DOUT-Pad2)") (class "Default")
      (node (ref "RGB2") (pin "2") (pinfunction "DOUT_2") (pintype "output"))
    )
    (net (code "140") (name "unconnected-(SW5-Pad1)") (class "Default")
      (node (ref "SW5") (pin "1") (pinfunction "1_1") (pintype "unspecified"))
    )
    (net (code "141") (name "unconnected-(SW5-Pad2)") (class "Default")
      (node (ref "SW5") (pin "2") (pinfunction "2_2") (pintype "unspecified"))
    )
    (net (code "142") (name "unconnected-(SW5-Pad7)") (class "Default")
      (node (ref "SW5") (pin "7") (pinfunction "7_7") (pintype "unspecified"))
    )
    (net (code "143") (name "unconnected-(SW5-Pad8)") (class "Default")
      (node (ref "SW5") (pin "8") (pinfunction "8_8") (pintype "unspecified"))
    )
    (net (code "144") (name "volt") (class "Default")
      (node (ref "IC1") (pin "30") (pinfunction "D38/A14/CS1_30") (pintype "unspecified"))
      (node (ref "R35") (pin "2") (pinfunction "2_2") (pintype "unspecified"))
      (node (ref "R36") (pin "2") (pinfunction "2_2") (pintype "unspecified"))
    )
  )
)
